# ai_breakout_TXB0108.net
KiCad netlist of a schematic drawn in EAGLE
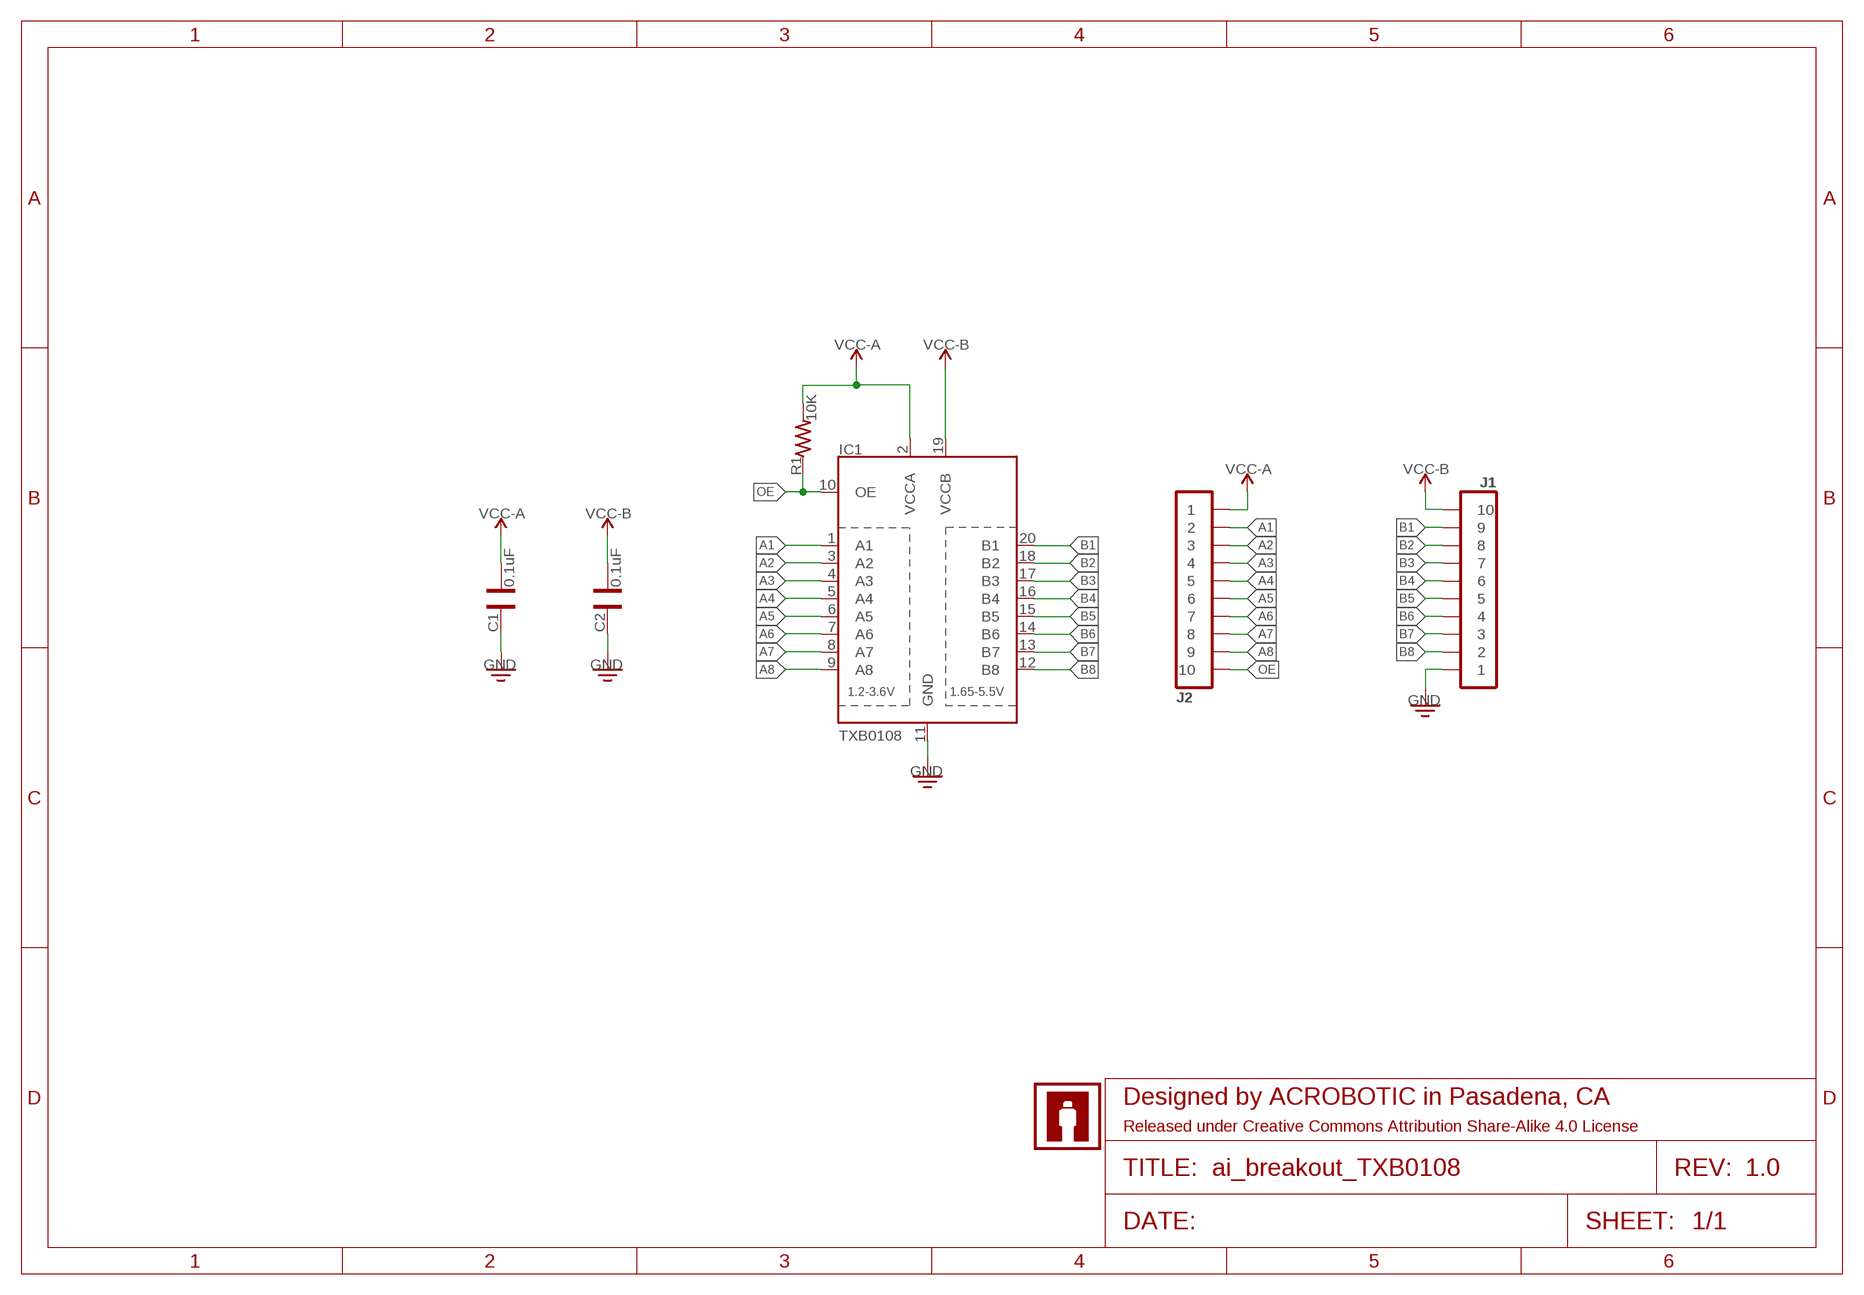
[diagram p0: schematic, sheet 1]

(export (version "E")
  (design (tool "Eeschema 10.0.6"))
  (components
    (comp (ref "C1")
      (value "0.1uF")
      (footprint "eagle-import:CAP-0603")
      (libsource (lib "eagle-import") (part "CAP0603"))
    )
    (comp (ref "C2")
      (value "0.1uF")
      (footprint "eagle-import:CAP-0603")
      (libsource (lib "eagle-import") (part "CAP0603"))
    )
    (comp (ref "FRAME1")
      (value "FRAME-LETTER")
      (footprint "eagle-import:CREATIVE-COMMONS")
      (fields (field (name "REV") "1.0"))
      (libsource (lib "eagle-import") (part "FRAME-LETTER"))
    )
    (comp (ref "IC1")
      (value "TXB0108")
      (footprint "eagle-import:TSSOP20")
      (libsource (lib "eagle-import") (part "TXB0108"))
    )
    (comp (ref "J1")
      (value "1X10")
      (footprint "eagle-import:1X10")
      (libsource (lib "eagle-import") (part "1X10"))
    )
    (comp (ref "J2")
      (value "1X10NOFIRST")
      (footprint "eagle-import:1X10-NOFIRST")
      (libsource (lib "eagle-import") (part "1X10NOFIRST"))
    )
    (comp (ref "R1")
      (value "10K")
      (footprint "eagle-import:RES-0603")
      (libsource (lib "eagle-import") (part "RES0603"))
    )
    (comp (ref "U$1")
      (value "AI-LOGOXS")
      (footprint "eagle-import:AI-LOGO-XS")
      (libsource (lib "eagle-import") (part "AI-LOGOXS"))
    )
    (comp (ref "U$2")
      (value "AI-LOGOXS")
      (footprint "eagle-import:AI-LOGO-XS")
      (libsource (lib "eagle-import") (part "AI-LOGOXS"))
    )
  )
  (nets
    (net (code "1") (name "A1") (class "Default")
      (node (ref "IC1") (pin "1") (pinfunction "A1_1") (pintype "bidirectional"))
      (node (ref "J2") (pin "2") (pinfunction "2_2") (pintype "bidirectional"))
    )
    (net (code "2") (name "A2") (class "Default")
      (node (ref "IC1") (pin "3") (pinfunction "A2_3") (pintype "bidirectional"))
      (node (ref "J2") (pin "3") (pinfunction "3_3") (pintype "bidirectional"))
    )
    (net (code "3") (name "A3") (class "Default")
      (node (ref "IC1") (pin "4") (pinfunction "A3_4") (pintype "bidirectional"))
      (node (ref "J2") (pin "4") (pinfunction "4_4") (pintype "bidirectional"))
    )
    (net (code "4") (name "A4") (class "Default")
      (node (ref "IC1") (pin "5") (pinfunction "A4_5") (pintype "bidirectional"))
      (node (ref "J2") (pin "5") (pinfunction "5_5") (pintype "bidirectional"))
    )
    (net (code "5") (name "A5") (class "Default")
      (node (ref "IC1") (pin "6") (pinfunction "A5_6") (pintype "bidirectional"))
      (node (ref "J2") (pin "6") (pinfunction "6_6") (pintype "bidirectional"))
    )
    (net (code "6") (name "A6") (class "Default")
      (node (ref "IC1") (pin "7") (pinfunction "A6_7") (pintype "bidirectional"))
      (node (ref "J2") (pin "7") (pinfunction "7_7") (pintype "bidirectional"))
    )
    (net (code "7") (name "A7") (class "Default")
      (node (ref "IC1") (pin "8") (pinfunction "A7_8") (pintype "bidirectional"))
      (node (ref "J2") (pin "8") (pinfunction "8_8") (pintype "bidirectional"))
    )
    (net (code "8") (name "A8") (class "Default")
      (node (ref "IC1") (pin "9") (pinfunction "A8_9") (pintype "bidirectional"))
      (node (ref "J2") (pin "9") (pinfunction "9_9") (pintype "bidirectional"))
    )
    (net (code "9") (name "B1") (class "Default")
      (node (ref "IC1") (pin "20") (pinfunction "B1_20") (pintype "bidirectional"))
      (node (ref "J1") (pin "9") (pinfunction "9_9") (pintype "bidirectional"))
    )
    (net (code "10") (name "B2") (class "Default")
      (node (ref "IC1") (pin "18") (pinfunction "B2_18") (pintype "bidirectional"))
      (node (ref "J1") (pin "8") (pinfunction "8_8") (pintype "bidirectional"))
    )
    (net (code "11") (name "B3") (class "Default")
      (node (ref "IC1") (pin "17") (pinfunction "B3_17") (pintype "bidirectional"))
      (node (ref "J1") (pin "7") (pinfunction "7_7") (pintype "bidirectional"))
    )
    (net (code "12") (name "B4") (class "Default")
      (node (ref "IC1") (pin "16") (pinfunction "B4_16") (pintype "bidirectional"))
      (node (ref "J1") (pin "6") (pinfunction "6_6") (pintype "bidirectional"))
    )
    (net (code "13") (name "B5") (class "Default")
      (node (ref "IC1") (pin "15") (pinfunction "B5_15") (pintype "bidirectional"))
      (node (ref "J1") (pin "5") (pinfunction "5_5") (pintype "bidirectional"))
    )
    (net (code "14") (name "B6") (class "Default")
      (node (ref "IC1") (pin "14") (pinfunction "B6_14") (pintype "bidirectional"))
      (node (ref "J1") (pin "4") (pinfunction "4_4") (pintype "bidirectional"))
    )
    (net (code "15") (name "B7") (class "Default")
      (node (ref "IC1") (pin "13") (pinfunction "B7_13") (pintype "bidirectional"))
      (node (ref "J1") (pin "3") (pinfunction "3_3") (pintype "bidirectional"))
    )
    (net (code "16") (name "B8") (class "Default")
      (node (ref "IC1") (pin "12") (pinfunction "B8_12") (pintype "bidirectional"))
      (node (ref "J1") (pin "2") (pinfunction "2_2") (pintype "bidirectional"))
    )
    (net (code "17") (name "GND") (class "Default")
      (node (ref "C1") (pin "2") (pinfunction "2_2") (pintype "passive"))
      (node (ref "C2") (pin "2") (pinfunction "2_2") (pintype "passive"))
      (node (ref "IC1") (pin "11") (pinfunction "GND_11") (pintype "bidirectional"))
      (node (ref "J1") (pin "1") (pinfunction "1_1") (pintype "bidirectional"))
    )
    (net (code "18") (name "OE") (class "Default")
      (node (ref "IC1") (pin "10") (pinfunction "OE_10") (pintype "bidirectional"))
      (node (ref "J2") (pin "10") (pinfunction "10_10") (pintype "bidirectional"))
      (node (ref "R1") (pin "1") (pinfunction "1_1") (pintype "passive"))
    )
    (net (code "19") (name "VCC-A") (class "Default")
      (node (ref "C1") (pin "1") (pinfunction "1_1") (pintype "passive"))
      (node (ref "IC1") (pin "2") (pinfunction "VCCA_2") (pintype "bidirectional"))
      (node (ref "J2") (pin "1") (pinfunction "1_1") (pintype "bidirectional"))
      (node (ref "R1") (pin "2") (pinfunction "2_2") (pintype "passive"))
    )
    (net (code "20") (name "VCC-B") (class "Default")
      (node (ref "C2") (pin "1") (pinfunction "1_1") (pintype "passive"))
      (node (ref "IC1") (pin "19") (pinfunction "VCCB_19") (pintype "bidirectional"))
      (node (ref "J1") (pin "10") (pinfunction "10_10") (pintype "bidirectional"))
    )
  )
)
